# Sxem.net
KiCad netlist of a schematic drawn in Altium Designer
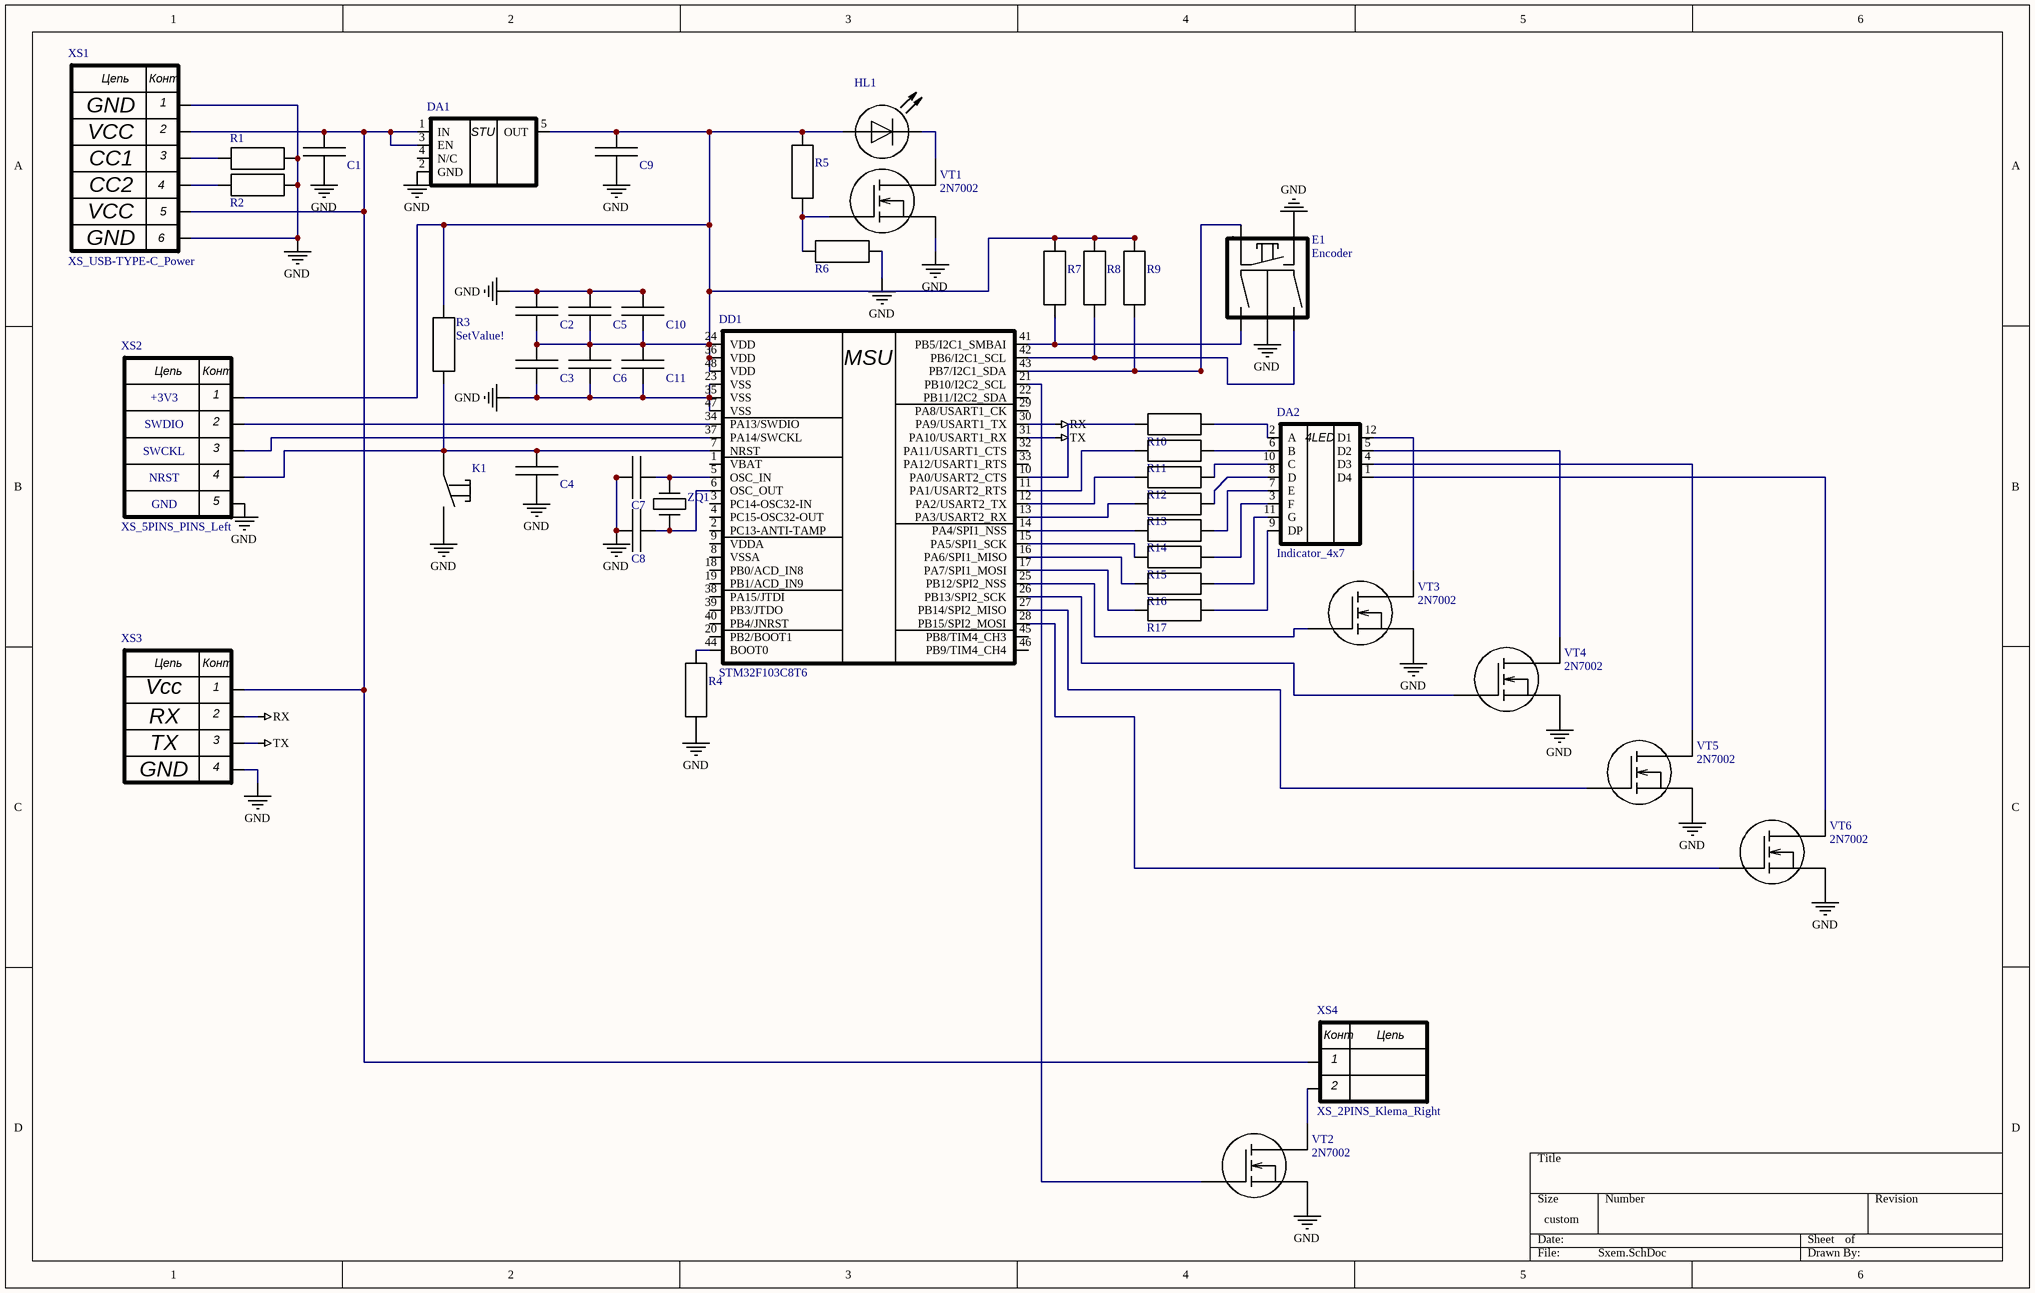
[diagram p0: Sxem.SchDoc]

(export (version "E")
  (design (tool "Eeschema 10.0.6"))
  (components
    (comp (ref "C1")
      (value "SetValue!")
      (footprint "C_SMD_0603")
      (libsource (lib "YGOLib") (part "C_Ceramic_SMD_0603"))
    )
    (comp (ref "C2")
      (value "SetValue!")
      (footprint "C_SMD_0603")
      (libsource (lib "YGOLib") (part "C_Ceramic_SMD_0603"))
    )
    (comp (ref "C3")
      (value "SetValue!")
      (footprint "C_SMD_0603")
      (libsource (lib "YGOLib") (part "C_Ceramic_SMD_0603"))
    )
    (comp (ref "C4")
      (value "SetValue!")
      (footprint "C_SMD_0603")
      (libsource (lib "YGOLib") (part "C_Ceramic_SMD_0603"))
    )
    (comp (ref "C5")
      (value "SetValue!")
      (footprint "C_SMD_0603")
      (libsource (lib "YGOLib") (part "C_Ceramic_SMD_0603"))
    )
    (comp (ref "C6")
      (value "SetValue!")
      (footprint "C_SMD_0603")
      (libsource (lib "YGOLib") (part "C_Ceramic_SMD_0603"))
    )
    (comp (ref "C7")
      (value "SetValue!")
      (footprint "C_SMD_0603")
      (libsource (lib "YGOLib") (part "C_Ceramic_SMD_0603"))
    )
    (comp (ref "C8")
      (value "SetValue!")
      (footprint "C_SMD_0603")
      (libsource (lib "YGOLib") (part "C_Ceramic_SMD_0603"))
    )
    (comp (ref "C9")
      (value "SetValue!")
      (footprint "C_SMD_0603")
      (libsource (lib "YGOLib") (part "C_Ceramic_SMD_0603"))
    )
    (comp (ref "C10")
      (value "SetValue!")
      (footprint "C_SMD_0603")
      (libsource (lib "YGOLib") (part "C_Ceramic_SMD_0603"))
    )
    (comp (ref "C11")
      (value "SetValue!")
      (footprint "C_SMD_0603")
      (libsource (lib "YGOLib") (part "C_Ceramic_SMD_0603"))
    )
    (comp (ref "DA1")
      (value "STU_5.5-3.3_NCP114ASN330T1G_SMD_TSOP-5")
      (footprint "TSOP-5")
      (libsource (lib "YGOLib") (part "STU_5.5-3.3_NCP114ASN330T1G_SMD_TSOP-5"))
    )
    (comp (ref "DA2")
      (value "Indicator_4x7")
      (footprint "4x7 Inditacor")
      (libsource (lib "YGOLib") (part "Indicator_4x7"))
    )
    (comp (ref "DD1")
      (value "STM32F103C8T6")
      (footprint "LQFP48")
      (libsource (lib "YGOLib") (part "STM32_F103c8t6_LQFP48"))
    )
    (comp (ref "E1") (value "Encoder") (footprint "ENCODER") (libsource (lib "YGOLib") (part "Encoder")))
    (comp (ref "HL1")
      (value "LED_SMD_RED")
      (footprint "LED_SMD_RED")
      (libsource (lib "YGOLib") (part "LED_SMD_RED"))
    )
    (comp (ref "K1")
      (value "BUT_SMD_KLS7-TS3608-5.0-180")
      (footprint "BUT_SMD_KLS7-TS3608-5.0-180")
      (libsource (lib "YGOLib") (part "BUT_SMD_KLS7-TS3608-5.0-180"))
    )
    (comp (ref "R1")
      (value "SetValue!")
      (footprint "R_SMD_0805")
      (libsource (lib "YGOLib") (part "R_SMD_0805"))
    )
    (comp (ref "R2")
      (value "SetValue!")
      (footprint "R_SMD_0805")
      (libsource (lib "YGOLib") (part "R_SMD_0805"))
    )
    (comp (ref "R3")
      (value "SetValue!")
      (footprint "R_SMD_0805")
      (libsource (lib "YGOLib") (part "R_SMD_0805"))
    )
    (comp (ref "R4")
      (value "SetValue!")
      (footprint "R_SMD_0805")
      (libsource (lib "YGOLib") (part "R_SMD_0805"))
    )
    (comp (ref "R5")
      (value "SetValue!")
      (footprint "R_SMD_0805")
      (libsource (lib "YGOLib") (part "R_SMD_0805"))
    )
    (comp (ref "R6")
      (value "SetValue!")
      (footprint "R_SMD_0805")
      (libsource (lib "YGOLib") (part "R_SMD_0805"))
    )
    (comp (ref "R7")
      (value "SetValue!")
      (footprint "R_SMD_0805")
      (libsource (lib "YGOLib") (part "R_SMD_0805"))
    )
    (comp (ref "R8")
      (value "SetValue!")
      (footprint "R_SMD_0805")
      (libsource (lib "YGOLib") (part "R_SMD_0805"))
    )
    (comp (ref "R9")
      (value "SetValue!")
      (footprint "R_SMD_0805")
      (libsource (lib "YGOLib") (part "R_SMD_0805"))
    )
    (comp (ref "R10")
      (value "SetValue!")
      (footprint "R_SMD_0805")
      (libsource (lib "YGOLib") (part "R_SMD_0805"))
    )
    (comp (ref "R11")
      (value "SetValue!")
      (footprint "R_SMD_0805")
      (libsource (lib "YGOLib") (part "R_SMD_0805"))
    )
    (comp (ref "R12")
      (value "SetValue!")
      (footprint "R_SMD_0805")
      (libsource (lib "YGOLib") (part "R_SMD_0805"))
    )
    (comp (ref "R13")
      (value "SetValue!")
      (footprint "R_SMD_0805")
      (libsource (lib "YGOLib") (part "R_SMD_0805"))
    )
    (comp (ref "R14")
      (value "SetValue!")
      (footprint "R_SMD_0805")
      (libsource (lib "YGOLib") (part "R_SMD_0805"))
    )
    (comp (ref "R15")
      (value "SetValue!")
      (footprint "R_SMD_0805")
      (libsource (lib "YGOLib") (part "R_SMD_0805"))
    )
    (comp (ref "R16")
      (value "SetValue!")
      (footprint "R_SMD_0805")
      (libsource (lib "YGOLib") (part "R_SMD_0805"))
    )
    (comp (ref "R17")
      (value "SetValue!")
      (footprint "R_SMD_0805")
      (libsource (lib "YGOLib") (part "R_SMD_0805"))
    )
    (comp (ref "VT1")
      (value "2N7002")
      (footprint "SOT23-3")
      (libsource (lib "YGOLib") (part "T_PI_N_2N7002_SMD_SOT-23-3_1"))
    )
    (comp (ref "VT2")
      (value "2N7002")
      (footprint "SOT23-3")
      (libsource (lib "YGOLib") (part "T_PI_N_2N7002_SMD_SOT-23-3_1"))
    )
    (comp (ref "VT3")
      (value "2N7002")
      (footprint "SOT23-3")
      (libsource (lib "YGOLib") (part "T_PI_N_2N7002_SMD_SOT-23-3_1"))
    )
    (comp (ref "VT4")
      (value "2N7002")
      (footprint "SOT23-3")
      (libsource (lib "YGOLib") (part "T_PI_N_2N7002_SMD_SOT-23-3_1"))
    )
    (comp (ref "VT5")
      (value "2N7002")
      (footprint "SOT23-3")
      (libsource (lib "YGOLib") (part "T_PI_N_2N7002_SMD_SOT-23-3_1"))
    )
    (comp (ref "VT6")
      (value "2N7002")
      (footprint "SOT23-3")
      (libsource (lib "YGOLib") (part "T_PI_N_2N7002_SMD_SOT-23-3_1"))
    )
    (comp (ref "XS1")
      (value "XS_USB-TYPE-C_Power")
      (footprint "USB-TYPE-C_6P")
      (libsource (lib "YGOLib") (part "XS_USB-TYPE-C_Power"))
    )
    (comp (ref "XS2")
      (value "XS_5PINS_PINS_Left")
      (footprint "5PINS")
      (libsource (lib "YGOLib") (part "XS_5PINS_PINS_Left"))
    )
    (comp (ref "XS3")
      (value "XS_4PINS_PINS_Left")
      (footprint "4PINS")
      (libsource (lib "YGOLib") (part "XS_4PINS_PINS_Left"))
    )
    (comp (ref "XS4")
      (value "XS_2PINS_Klema_Right")
      (footprint "XS_2PINS")
      (libsource (lib "YGOLib") (part "XS_2PINS_Klema_Right"))
    )
    (comp (ref "ZQ1")
      (value "Quartz_8MGz_THT_HC-49S")
      (footprint "Quartz")
      (libsource (lib "YGOLib") (part "Quartz_8MGz_THT_HC-49S"))
    )
  )
  (nets
    (net (code "1") (name "GND") (class "Default")
      (node (ref "C1") (pin "1") (pinfunction "1_1") (pintype "passive"))
      (node (ref "C10") (pin "2") (pinfunction "2_2") (pintype "passive"))
      (node (ref "C11") (pin "1") (pinfunction "1_1") (pintype "passive"))
      (node (ref "C2") (pin "2") (pinfunction "2_2") (pintype "passive"))
      (node (ref "C3") (pin "1") (pinfunction "1_1") (pintype "passive"))
      (node (ref "C4") (pin "1") (pinfunction "1_1") (pintype "passive"))
      (node (ref "C5") (pin "2") (pinfunction "2_2") (pintype "passive"))
      (node (ref "C6") (pin "1") (pinfunction "1_1") (pintype "passive"))
      (node (ref "C7") (pin "2") (pinfunction "2_2") (pintype "passive"))
      (node (ref "C8") (pin "2") (pinfunction "2_2") (pintype "passive"))
      (node (ref "C9") (pin "1") (pinfunction "1_1") (pintype "passive"))
      (node (ref "DA1") (pin "2") (pinfunction "GND_2") (pintype "passive"))
      (node (ref "DD1") (pin "23") (pinfunction "VSS_23") (pintype "passive"))
      (node (ref "DD1") (pin "35") (pinfunction "VSS_35") (pintype "passive"))
      (node (ref "DD1") (pin "47") (pinfunction "VSS_47") (pintype "passive"))
      (node (ref "E1") (pin "2") (pinfunction "F_2") (pintype "passive"))
      (node (ref "E1") (pin "5") (pinfunction "GND_5") (pintype "passive"))
      (node (ref "K1") (pin "2") (pinfunction "2_2") (pintype "passive"))
      (node (ref "R1") (pin "2") (pinfunction "2_2") (pintype "passive"))
      (node (ref "R2") (pin "2") (pinfunction "2_2") (pintype "passive"))
      (node (ref "R4") (pin "1") (pinfunction "1_1") (pintype "passive"))
      (node (ref "R6") (pin "2") (pinfunction "2_2") (pintype "passive"))
      (node (ref "VT1") (pin "2") (pinfunction "И_2") (pintype "passive"))
      (node (ref "VT2") (pin "2") (pinfunction "И_2") (pintype "passive"))
      (node (ref "VT3") (pin "2") (pinfunction "И_2") (pintype "passive"))
      (node (ref "VT4") (pin "2") (pinfunction "И_2") (pintype "passive"))
      (node (ref "VT5") (pin "2") (pinfunction "И_2") (pintype "passive"))
      (node (ref "VT6") (pin "2") (pinfunction "И_2") (pintype "passive"))
      (node (ref "XS1") (pin "1") (pinfunction "1_1") (pintype "power_in"))
      (node (ref "XS1") (pin "6") (pinfunction "6_6") (pintype "passive"))
      (node (ref "XS2") (pin "5") (pinfunction "5_5") (pintype "passive"))
      (node (ref "XS3") (pin "4") (pinfunction "4_4") (pintype "passive"))
    )
    (net (code "2") (name "Net-(DA1-EN)") (class "Default")
      (node (ref "C1") (pin "2") (pinfunction "2_2") (pintype "passive"))
      (node (ref "DA1") (pin "1") (pinfunction "IN_1") (pintype "passive"))
      (node (ref "DA1") (pin "3") (pinfunction "EN_3") (pintype "passive"))
      (node (ref "XS1") (pin "2") (pinfunction "2_2") (pintype "power_in"))
      (node (ref "XS1") (pin "5") (pinfunction "5_5") (pintype "passive"))
      (node (ref "XS3") (pin "1") (pinfunction "1_1") (pintype "power_in"))
      (node (ref "XS4") (pin "1") (pinfunction "1_1") (pintype "power_in"))
    )
    (net (code "3") (name "Net-(DA1-OUT)") (class "Default")
      (node (ref "C10") (pin "1") (pinfunction "1_1") (pintype "passive"))
      (node (ref "C11") (pin "2") (pinfunction "2_2") (pintype "passive"))
      (node (ref "C2") (pin "1") (pinfunction "1_1") (pintype "passive"))
      (node (ref "C3") (pin "2") (pinfunction "2_2") (pintype "passive"))
      (node (ref "C5") (pin "1") (pinfunction "1_1") (pintype "passive"))
      (node (ref "C6") (pin "2") (pinfunction "2_2") (pintype "passive"))
      (node (ref "C9") (pin "2") (pinfunction "2_2") (pintype "passive"))
      (node (ref "DA1") (pin "5") (pinfunction "OUT_5") (pintype "passive"))
      (node (ref "DD1") (pin "24") (pinfunction "VDD_24") (pintype "passive"))
      (node (ref "DD1") (pin "36") (pinfunction "VDD_36") (pintype "passive"))
      (node (ref "DD1") (pin "48") (pinfunction "VDD_48") (pintype "passive"))
      (node (ref "HL1") (pin "1") (pinfunction "1_1") (pintype "power_in"))
      (node (ref "R3") (pin "2") (pinfunction "2_2") (pintype "passive"))
      (node (ref "R5") (pin "2") (pinfunction "2_2") (pintype "passive"))
      (node (ref "R7") (pin "2") (pinfunction "2_2") (pintype "passive"))
      (node (ref "R8") (pin "2") (pinfunction "2_2") (pintype "passive"))
      (node (ref "R9") (pin "2") (pinfunction "2_2") (pintype "passive"))
      (node (ref "XS2") (pin "1") (pinfunction "1_1") (pintype "power_in"))
    )
    (net (code "4") (name "Net-(DA2-A)") (class "Default")
      (node (ref "DA2") (pin "2") (pinfunction "A_2") (pintype "passive"))
      (node (ref "R10") (pin "1") (pinfunction "1_1") (pintype "passive"))
    )
    (net (code "5") (name "Net-(DA2-B)") (class "Default")
      (node (ref "DA2") (pin "6") (pinfunction "B_6") (pintype "passive"))
      (node (ref "R11") (pin "1") (pinfunction "1_1") (pintype "passive"))
    )
    (net (code "6") (name "Net-(DA2-C)") (class "Default")
      (node (ref "DA2") (pin "10") (pinfunction "C_10") (pintype "passive"))
      (node (ref "R12") (pin "1") (pinfunction "1_1") (pintype "passive"))
    )
    (net (code "7") (name "Net-(DA2-D)") (class "Default")
      (node (ref "DA2") (pin "8") (pinfunction "D_8") (pintype "passive"))
      (node (ref "R13") (pin "1") (pinfunction "1_1") (pintype "passive"))
    )
    (net (code "8") (name "Net-(DA2-D1)") (class "Default")
      (node (ref "DA2") (pin "12") (pinfunction "D1_12") (pintype "passive"))
      (node (ref "VT3") (pin "3") (pinfunction "C_3") (pintype "passive"))
    )
    (net (code "9") (name "Net-(DA2-D2)") (class "Default")
      (node (ref "DA2") (pin "5") (pinfunction "D2_5") (pintype "passive"))
      (node (ref "VT4") (pin "3") (pinfunction "C_3") (pintype "passive"))
    )
    (net (code "10") (name "Net-(DA2-D3)") (class "Default")
      (node (ref "DA2") (pin "4") (pinfunction "D3_4") (pintype "passive"))
      (node (ref "VT5") (pin "3") (pinfunction "C_3") (pintype "passive"))
    )
    (net (code "11") (name "Net-(DA2-D4)") (class "Default")
      (node (ref "DA2") (pin "1") (pinfunction "D4_1") (pintype "passive"))
      (node (ref "VT6") (pin "3") (pinfunction "C_3") (pintype "passive"))
    )
    (net (code "12") (name "Net-(DA2-DP)") (class "Default")
      (node (ref "DA2") (pin "9") (pinfunction "DP_9") (pintype "passive"))
      (node (ref "R17") (pin "1") (pinfunction "1_1") (pintype "passive"))
    )
    (net (code "13") (name "Net-(DA2-E)") (class "Default")
      (node (ref "DA2") (pin "7") (pinfunction "E_7") (pintype "passive"))
      (node (ref "R14") (pin "1") (pinfunction "1_1") (pintype "passive"))
    )
    (net (code "14") (name "Net-(DA2-F)") (class "Default")
      (node (ref "DA2") (pin "3") (pinfunction "F_3") (pintype "passive"))
      (node (ref "R15") (pin "1") (pinfunction "1_1") (pintype "passive"))
    )
    (net (code "15") (name "Net-(DA2-G)") (class "Default")
      (node (ref "DA2") (pin "11") (pinfunction "G_11") (pintype "passive"))
      (node (ref "R16") (pin "1") (pinfunction "1_1") (pintype "passive"))
    )
    (net (code "16") (name "Net-(DD1-BOOT0)") (class "Default")
      (node (ref "DD1") (pin "44") (pinfunction "BOOT0_44") (pintype "passive"))
      (node (ref "R4") (pin "2") (pinfunction "2_2") (pintype "passive"))
    )
    (net (code "17") (name "Net-(DD1-NRST)") (class "Default")
      (node (ref "C4") (pin "2") (pinfunction "2_2") (pintype "passive"))
      (node (ref "DD1") (pin "7") (pinfunction "NRST_7") (pintype "passive"))
      (node (ref "K1") (pin "1") (pinfunction "1_1") (pintype "passive"))
      (node (ref "R3") (pin "1") (pinfunction "1_1") (pintype "passive"))
      (node (ref "XS2") (pin "4") (pinfunction "4_4") (pintype "passive"))
    )
    (net (code "18") (name "Net-(DD1-OSC_IN)") (class "Default")
      (node (ref "C7") (pin "1") (pinfunction "1_1") (pintype "passive"))
      (node (ref "DD1") (pin "5") (pinfunction "OSC_IN_5") (pintype "passive"))
      (node (ref "ZQ1") (pin "2") (pinfunction "2_2") (pintype "passive"))
    )
    (net (code "19") (name "Net-(DD1-OSC_OUT)") (class "Default")
      (node (ref "C8") (pin "1") (pinfunction "1_1") (pintype "passive"))
      (node (ref "DD1") (pin "6") (pinfunction "OSC_OUT_6") (pintype "passive"))
      (node (ref "ZQ1") (pin "1") (pinfunction "1_1") (pintype "passive"))
    )
    (net (code "20") (name "Net-(DD1-PA0{slash}USART2_CTS)") (class "Default")
      (node (ref "DD1") (pin "10") (pinfunction "PA0/USART2_CTS_10") (pintype "passive"))
      (node (ref "R10") (pin "2") (pinfunction "2_2") (pintype "passive"))
    )
    (net (code "21") (name "Net-(DD1-PA1{slash}USART2_RTS)") (class "Default")
      (node (ref "DD1") (pin "11") (pinfunction "PA1/USART2_RTS_11") (pintype "passive"))
      (node (ref "R11") (pin "2") (pinfunction "2_2") (pintype "passive"))
    )
    (net (code "22") (name "Net-(DD1-PA2{slash}USART2_TX)") (class "Default")
      (node (ref "DD1") (pin "12") (pinfunction "PA2/USART2_TX_12") (pintype "passive"))
      (node (ref "R12") (pin "2") (pinfunction "2_2") (pintype "passive"))
    )
    (net (code "23") (name "Net-(DD1-PA3{slash}USART2_RX)") (class "Default")
      (node (ref "DD1") (pin "13") (pinfunction "PA3/USART2_RX_13") (pintype "passive"))
      (node (ref "R13") (pin "2") (pinfunction "2_2") (pintype "passive"))
    )
    (net (code "24") (name "Net-(DD1-PA4{slash}SPI1_NSS)") (class "Default")
      (node (ref "DD1") (pin "14") (pinfunction "PA4/SPI1_NSS_14") (pintype "passive"))
      (node (ref "R14") (pin "2") (pinfunction "2_2") (pintype "passive"))
    )
    (net (code "25") (name "Net-(DD1-PA5{slash}SPI1_SCK)") (class "Default")
      (node (ref "DD1") (pin "15") (pinfunction "PA5/SPI1_SCK_15") (pintype "passive"))
      (node (ref "R15") (pin "2") (pinfunction "2_2") (pintype "passive"))
    )
    (net (code "26") (name "Net-(DD1-PA6{slash}SPI1_MISO)") (class "Default")
      (node (ref "DD1") (pin "16") (pinfunction "PA6/SPI1_MISO_16") (pintype "passive"))
      (node (ref "R16") (pin "2") (pinfunction "2_2") (pintype "passive"))
    )
    (net (code "27") (name "Net-(DD1-PA7{slash}SPI1_MOSI)") (class "Default")
      (node (ref "DD1") (pin "17") (pinfunction "PA7/SPI1_MOSI_17") (pintype "passive"))
      (node (ref "R17") (pin "2") (pinfunction "2_2") (pintype "passive"))
    )
    (net (code "28") (name "Net-(DD1-PA13{slash}SWDIO)") (class "Default")
      (node (ref "DD1") (pin "34") (pinfunction "PA13/SWDIO_34") (pintype "passive"))
      (node (ref "XS2") (pin "2") (pinfunction "2_2") (pintype "power_in"))
    )
    (net (code "29") (name "Net-(DD1-PA14{slash}SWCKL)") (class "Default")
      (node (ref "DD1") (pin "37") (pinfunction "PA14/SWCKL_37") (pintype "passive"))
      (node (ref "XS2") (pin "3") (pinfunction "3_3") (pintype "passive"))
    )
    (net (code "30") (name "Net-(DD1-PB5{slash}I2C1_SMBAI)") (class "Default")
      (node (ref "DD1") (pin "41") (pinfunction "PB5/I2C1_SMBAI_41") (pintype "passive"))
      (node (ref "E1") (pin "3") (pinfunction "A_3") (pintype "passive"))
      (node (ref "R7") (pin "1") (pinfunction "1_1") (pintype "passive"))
    )
    (net (code "31") (name "Net-(DD1-PB6{slash}I2C1_SCL)") (class "Default")
      (node (ref "DD1") (pin "42") (pinfunction "PB6/I2C1_SCL_42") (pintype "passive"))
      (node (ref "E1") (pin "4") (pinfunction "B_4") (pintype "passive"))
      (node (ref "R8") (pin "1") (pinfunction "1_1") (pintype "passive"))
    )
    (net (code "32") (name "Net-(DD1-PB7{slash}I2C1_SDA)") (class "Default")
      (node (ref "DD1") (pin "43") (pinfunction "PB7/I2C1_SDA_43") (pintype "passive"))
      (node (ref "E1") (pin "1") (pinfunction "E_1") (pintype "passive"))
      (node (ref "R9") (pin "1") (pinfunction "1_1") (pintype "passive"))
    )
    (net (code "33") (name "Net-(DD1-PB10{slash}I2C2_SCL)") (class "Default")
      (node (ref "DD1") (pin "21") (pinfunction "PB10/I2C2_SCL_21") (pintype "passive"))
      (node (ref "VT2") (pin "1") (pinfunction "З_1") (pintype "passive"))
    )
    (net (code "34") (name "Net-(DD1-PB12{slash}SPI2_NSS)") (class "Default")
      (node (ref "DD1") (pin "25") (pinfunction "PB12/SPI2_NSS_25") (pintype "passive"))
      (node (ref "VT3") (pin "1") (pinfunction "З_1") (pintype "passive"))
    )
    (net (code "35") (name "Net-(DD1-PB13{slash}SPI2_SCK)") (class "Default")
      (node (ref "DD1") (pin "26") (pinfunction "PB13/SPI2_SCK_26") (pintype "passive"))
      (node (ref "VT4") (pin "1") (pinfunction "З_1") (pintype "passive"))
    )
    (net (code "36") (name "Net-(DD1-PB14{slash}SPI2_MISO)") (class "Default")
      (node (ref "DD1") (pin "27") (pinfunction "PB14/SPI2_MISO_27") (pintype "passive"))
      (node (ref "VT5") (pin "1") (pinfunction "З_1") (pintype "passive"))
    )
    (net (code "37") (name "Net-(DD1-PB15{slash}SPI2_MOSI)") (class "Default")
      (node (ref "DD1") (pin "28") (pinfunction "PB15/SPI2_MOSI_28") (pintype "passive"))
      (node (ref "VT6") (pin "1") (pinfunction "З_1") (pintype "passive"))
    )
    (net (code "38") (name "Net-(R1-Pad1)") (class "Default")
      (node (ref "R1") (pin "1") (pinfunction "1_1") (pintype "passive"))
      (node (ref "XS1") (pin "3") (pinfunction "3_3") (pintype "passive"))
    )
    (net (code "39") (name "Net-(R2-Pad1)") (class "Default")
      (node (ref "R2") (pin "1") (pinfunction "1_1") (pintype "passive"))
      (node (ref "XS1") (pin "4") (pinfunction "4_4") (pintype "passive"))
    )
    (net (code "40") (name "Net-(VT1-C)") (class "Default")
      (node (ref "HL1") (pin "2") (pinfunction "2_2") (pintype "power_in"))
      (node (ref "VT1") (pin "3") (pinfunction "C_3") (pintype "passive"))
    )
    (net (code "41") (name "Net-(VT1-З)") (class "Default")
      (node (ref "R5") (pin "1") (pinfunction "1_1") (pintype "passive"))
      (node (ref "R6") (pin "1") (pinfunction "1_1") (pintype "passive"))
      (node (ref "VT1") (pin "1") (pinfunction "З_1") (pintype "passive"))
    )
    (net (code "42") (name "Net-(VT2-C)") (class "Default")
      (node (ref "VT2") (pin "3") (pinfunction "C_3") (pintype "passive"))
      (node (ref "XS4") (pin "2") (pinfunction "2_2") (pintype "power_in"))
    )
    (net (code "43") (name "RX") (class "Default")
      (node (ref "DD1") (pin "30") (pinfunction "PA9/USART1_TX_30") (pintype "passive"))
      (node (ref "XS3") (pin "2") (pinfunction "2_2") (pintype "power_in"))
    )
    (net (code "44") (name "TX") (class "Default")
      (node (ref "DD1") (pin "31") (pinfunction "PA10/USART1_RX_31") (pintype "passive"))
      (node (ref "XS3") (pin "3") (pinfunction "3_3") (pintype "passive"))
    )
    (net (code "45") (name "unconnected-(DA1-N{slash}C-Pad4)") (class "Default")
      (node (ref "DA1") (pin "4") (pinfunction "N/C_4") (pintype "passive"))
    )
    (net (code "46") (name "unconnected-(DD1-PA8{slash}USART1_CK-Pad29)") (class "Default")
      (node (ref "DD1") (pin "29") (pinfunction "PA8/USART1_CK_29") (pintype "passive"))
    )
    (net (code "47") (name "unconnected-(DD1-PA11{slash}USART1_CTS-Pad32)") (class "Default")
      (node (ref "DD1") (pin "32") (pinfunction "PA11/USART1_CTS_32") (pintype "passive"))
    )
    (net (code "48") (name "unconnected-(DD1-PA12{slash}USART1_RTS-Pad33)") (class "Default")
      (node (ref "DD1") (pin "33") (pinfunction "PA12/USART1_RTS_33") (pintype "passive"))
    )
    (net (code "49") (name "unconnected-(DD1-PA15{slash}JTDI-Pad38)") (class "Default")
      (node (ref "DD1") (pin "38") (pinfunction "PA15/JTDI_38") (pintype "passive"))
    )
    (net (code "50") (name "unconnected-(DD1-PB0{slash}ACD_IN8-Pad18)") (class "Default")
      (node (ref "DD1") (pin "18") (pinfunction "PB0/ACD_IN8_18") (pintype "passive"))
    )
    (net (code "51") (name "unconnected-(DD1-PB1{slash}ACD_IN9-Pad19)") (class "Default")
      (node (ref "DD1") (pin "19") (pinfunction "PB1/ACD_IN9_19") (pintype "passive"))
    )
    (net (code "52") (name "unconnected-(DD1-PB2{slash}BOOT1-Pad20)") (class "Default")
      (node (ref "DD1") (pin "20") (pinfunction "PB2/BOOT1_20") (pintype "passive"))
    )
    (net (code "53") (name "unconnected-(DD1-PB3{slash}JTDO-Pad39)") (class "Default")
      (node (ref "DD1") (pin "39") (pinfunction "PB3/JTDO_39") (pintype "passive"))
    )
    (net (code "54") (name "unconnected-(DD1-PB4{slash}JNRST-Pad40)") (class "Default")
      (node (ref "DD1") (pin "40") (pinfunction "PB4/JNRST_40") (pintype "passive"))
    )
    (net (code "55") (name "unconnected-(DD1-PB8{slash}TIM4_CH3-Pad45)") (class "Default")
      (node (ref "DD1") (pin "45") (pinfunction "PB8/TIM4_CH3_45") (pintype "passive"))
    )
    (net (code "56") (name "unconnected-(DD1-PB9{slash}TIM4_CH4-Pad46)") (class "Default")
      (node (ref "DD1") (pin "46") (pinfunction "PB9/TIM4_CH4_46") (pintype "passive"))
    )
    (net (code "57") (name "unconnected-(DD1-PB11{slash}I2C2_SDA-Pad22)") (class "Default")
      (node (ref "DD1") (pin "22") (pinfunction "PB11/I2C2_SDA_22") (pintype "passive"))
    )
    (net (code "58") (name "unconnected-(DD1-PC13-ANTI-TAMP-Pad2)") (class "Default")
      (node (ref "DD1") (pin "2") (pinfunction "PC13-ANTI-TAMP_2") (pintype "passive"))
    )
    (net (code "59") (name "unconnected-(DD1-PC14-OSC32-IN-Pad3)") (class "Default")
      (node (ref "DD1") (pin "3") (pinfunction "PC14-OSC32-IN_3") (pintype "passive"))
    )
    (net (code "60") (name "unconnected-(DD1-PC15-OSC32-OUT-Pad4)") (class "Default")
      (node (ref "DD1") (pin "4") (pinfunction "PC15-OSC32-OUT_4") (pintype "passive"))
    )
    (net (code "61") (name "unconnected-(DD1-VBAT-Pad1)") (class "Default")
      (node (ref "DD1") (pin "1") (pinfunction "VBAT_1") (pintype "passive"))
    )
    (net (code "62") (name "unconnected-(DD1-VDDA-Pad9)") (class "Default")
      (node (ref "DD1") (pin "9") (pinfunction "VDDA_9") (pintype "passive"))
    )
    (net (code "63") (name "unconnected-(DD1-VSSA-Pad8)") (class "Default")
      (node (ref "DD1") (pin "8") (pinfunction "VSSA_8") (pintype "passive"))
    )
  )
)
